# CHRG_2xCell_MCP73213-B6SIMF.net
KiCad netlist of a schematic drawn in Altium Designer
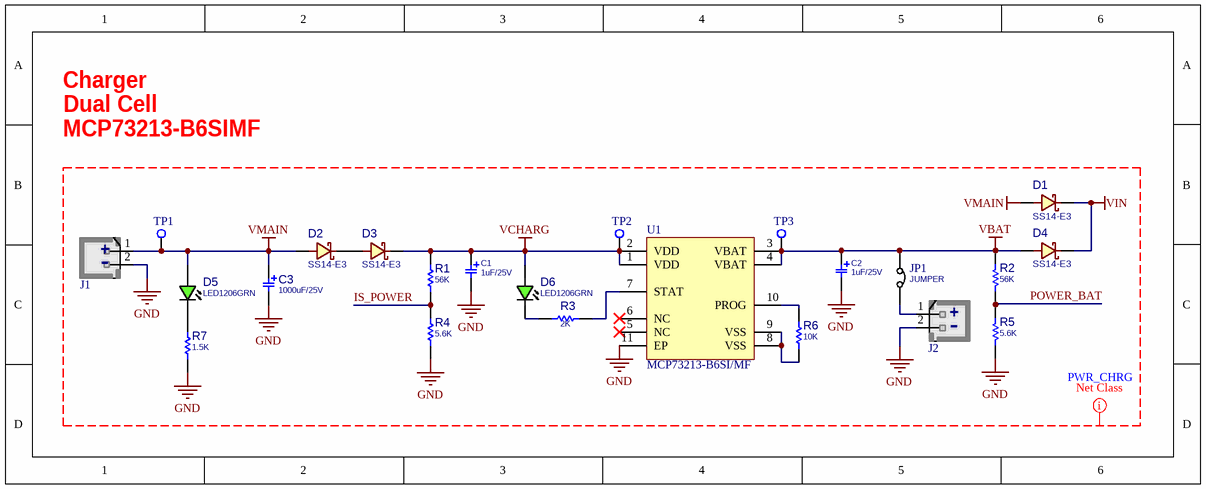
[diagram p0: CHRG 2xCell MCP73213-B6SIMF.SchDoc]

(export (version "E")
  (design (tool "Eeschema 10.0.6"))
  (components
    (comp (ref "C1")
      (value "1uF/25V")
      (footprint "C_TN_A")
      (description "CAP, SMD, TAN")
      (libsource (lib "Passive") (part "CAP_SMD_TAN"))
    )
    (comp (ref "C2")
      (value "1uF/25V")
      (footprint "C_TN_A")
      (description "CAP, SMD, TAN")
      (libsource (lib "Passive") (part "CAP_SMD_TAN"))
    )
    (comp (ref "C3")
      (value "1000uF/25V")
      (footprint "C_EL_10X20")
      (description "CAP, THD, ELEC")
      (fields (field (name "MANF_P#") "MANF_PART#") (field (name "MANF") "MANF"))
      (libsource (lib "Passive") (part "CAP_THD_EL"))
    )
    (comp (ref "D1")
      (value "SS14-E3")
      (footprint "D_SMA")
      (description "DIODE, SCHOTTKY, 40V, 1A")
      (fields (field (name "MANF") "Vishay"))
      (libsource (lib "Diode") (part "DIODE_SMD_SCHOTTKY_SS14-E3"))
    )
    (comp (ref "D2")
      (value "SS14-E3")
      (footprint "D_SMA")
      (description "DIODE, SCHOTTKY, 40V, 1A")
      (fields (field (name "MANF") "Vishay"))
      (libsource (lib "Diode") (part "DIODE_SMD_SCHOTTKY_SS14-E3"))
    )
    (comp (ref "D3")
      (value "SS14-E3")
      (footprint "D_SMA")
      (description "DIODE, SCHOTTKY, 40V, 1A")
      (fields (field (name "MANF") "Vishay"))
      (libsource (lib "Diode") (part "DIODE_SMD_SCHOTTKY_SS14-E3"))
    )
    (comp (ref "D4")
      (value "SS14-E3")
      (footprint "D_SMA")
      (description "DIODE, SCHOTTKY, 40V, 1A")
      (fields (field (name "MANF") "Vishay"))
      (libsource (lib "Diode") (part "DIODE_SMD_SCHOTTKY_SS14-E3"))
    )
    (comp (ref "D5")
      (value "LED1206GRN")
      (footprint "LED1206GRN")
      (description "LED, SMD, 1206, GREEN")
      (libsource (lib "LED") (part "LED_SMD_1206_GRN"))
    )
    (comp (ref "D6")
      (value "LED1206GRN")
      (footprint "LED1206GRN")
      (description "LED, SMD, 1206, GREEN")
      (libsource (lib "LED") (part "LED_SMD_1206_GRN"))
    )
    (comp (ref "J1")
      (value "HHDR_2")
      (footprint "XH_2")
      (description "CONN, CNT, pitch: 2.54mm, 2POS")
      (libsource (lib "PW Components") (part "CONN_PW_POWER_CNT_254_1X2"))
    )
    (comp (ref "J2")
      (value "HHDR_2")
      (footprint "XH_2")
      (description "CONN, CNT, pitch: 2.54mm, 2POS")
      (libsource (lib "") (part "CONN_PW_POWER_CNT_254_1X2_1"))
    )
    (comp (ref "JP1")
      (value "JUMPER")
      (footprint "JP_2_BLK")
      (description "JUMPER, HEADER 2PIN")
      (fields (field (name "MANF") "MANF") (field (name "MANF_P#") "MANF_P#"))
      (libsource (lib "PW Components") (part "JUMPER_HDR_2P"))
    )
    (comp (ref "R1")
      (value "56K")
      (footprint "R0603S")
      (description "RES, SMD")
      (fields (field (name "MANF_P#") "RK73H1ETTP4701F") (field (name "MANF") "KOA SPEER"))
      (libsource (lib "Passive") (part "RES_SMD"))
    )
    (comp (ref "R2")
      (value "56K")
      (footprint "R0603S")
      (description "RES, SMD")
      (fields (field (name "MANF_P#") "RK73H1ETTP4701F") (field (name "MANF") "KOA SPEER"))
      (libsource (lib "Passive") (part "RES_SMD"))
    )
    (comp (ref "R3")
      (value "2K")
      (footprint "R0603S")
      (description "RES, SMD")
      (fields (field (name "MANF_P#") "RK73H1ETTP4701F") (field (name "MANF") "KOA SPEER"))
      (libsource (lib "Passive") (part "RES_SMD"))
    )
    (comp (ref "R4")
      (value "5.6K")
      (footprint "R0603S")
      (description "RES, SMD")
      (fields (field (name "MANF_P#") "RK73H1ETTP4701F") (field (name "MANF") "KOA SPEER"))
      (libsource (lib "Passive") (part "RES_SMD"))
    )
    (comp (ref "R5")
      (value "5.6K")
      (footprint "R0603S")
      (description "RES, SMD")
      (fields (field (name "MANF_P#") "RK73H1ETTP4701F") (field (name "MANF") "KOA SPEER"))
      (libsource (lib "Passive") (part "RES_SMD"))
    )
    (comp (ref "R6")
      (value "10K")
      (footprint "R0603S")
      (description "RES, SMD")
      (fields (field (name "MANF_P#") "RK73H1ETTP4701F") (field (name "MANF") "KOA SPEER"))
      (libsource (lib "Passive") (part "RES_SMD"))
    )
    (comp (ref "R7")
      (value "1.5K")
      (footprint "R0603S")
      (description "RES, SMD")
      (fields (field (name "MANF_P#") "RK73H1ETTP4701F") (field (name "MANF") "KOA SPEER"))
      (libsource (lib "Passive") (part "RES_SMD"))
    )
    (comp (ref "TP1")
      (value "Test Point")
      (footprint "TPSMD_C1")
      (libsource (lib "Passives") (part "Test Point"))
    )
    (comp (ref "TP2")
      (value "Test Point")
      (footprint "TPSMD_C1")
      (libsource (lib "Passives") (part "Test Point"))
    )
    (comp (ref "TP3")
      (value "Test Point")
      (footprint "TPSMD_C1")
      (libsource (lib "Passives") (part "Test Point"))
    )
    (comp (ref "U1")
      (value "MCP73213-B6SI/MF")
      (footprint "SON50_10T_3X3")
      (fields (field (name "PUBLISHER") "Altium Limited"))
      (libsource (lib "Microchip Power Mgt Battery Management") (part "MCP73213-B6SI/MF"))
    )
  )
  (nets
    (net (code "1") (name "/IS_POWER") (class "Default")
      (node (ref "R1") (pin "1") (pinfunction "1_1") (pintype "passive"))
      (node (ref "R4") (pin "2") (pinfunction "2_2") (pintype "passive"))
    )
    (net (code "2") (name "/POWER_BAT") (class "Default")
      (node (ref "R2") (pin "1") (pinfunction "1_1") (pintype "passive"))
      (node (ref "R5") (pin "2") (pinfunction "2_2") (pintype "passive"))
    )
    (net (code "3") (name "GND") (class "Default")
      (node (ref "C1") (pin "2") (pinfunction "2_2") (pintype "passive"))
      (node (ref "C2") (pin "2") (pinfunction "2_2") (pintype "passive"))
      (node (ref "C3") (pin "2") (pinfunction "2_2") (pintype "passive"))
      (node (ref "J1") (pin "2") (pinfunction "2_2") (pintype "passive"))
      (node (ref "J2") (pin "2") (pinfunction "2_2") (pintype "passive"))
      (node (ref "R4") (pin "1") (pinfunction "1_1") (pintype "passive"))
      (node (ref "R5") (pin "1") (pinfunction "1_1") (pintype "passive"))
      (node (ref "R7") (pin "1") (pinfunction "1_1") (pintype "passive"))
      (node (ref "U1") (pin "11") (pinfunction "EP_11") (pintype "passive"))
    )
    (net (code "4") (name "Net-(D2-Pad2)") (class "Default")
      (node (ref "D2") (pin "2") (pinfunction "2_2") (pintype "passive"))
      (node (ref "D3") (pin "1") (pinfunction "1_1") (pintype "passive"))
    )
    (net (code "5") (name "Net-(D5-CATHODE)") (class "Default")
      (node (ref "D5") (pin "2") (pinfunction "CATHODE_2") (pintype "passive"))
      (node (ref "R7") (pin "2") (pinfunction "2_2") (pintype "passive"))
    )
    (net (code "6") (name "Net-(D6-CATHODE)") (class "Default")
      (node (ref "D6") (pin "2") (pinfunction "CATHODE_2") (pintype "passive"))
      (node (ref "R3") (pin "2") (pinfunction "2_2") (pintype "passive"))
    )
    (net (code "7") (name "Net-(J2-Pad1)") (class "Default")
      (node (ref "J2") (pin "1") (pinfunction "1_1") (pintype "passive"))
      (node (ref "JP1") (pin "2") (pinfunction "2_2") (pintype "passive"))
    )
    (net (code "8") (name "Net-(R6-Pad2)") (class "Default")
      (node (ref "R6") (pin "2") (pinfunction "2_2") (pintype "passive"))
      (node (ref "U1") (pin "8") (pinfunction "VSS_8") (pintype "passive"))
      (node (ref "U1") (pin "9") (pinfunction "VSS_9") (pintype "passive"))
    )
    (net (code "9") (name "Net-(U1-PROG)") (class "Default")
      (node (ref "R6") (pin "1") (pinfunction "1_1") (pintype "passive"))
      (node (ref "U1") (pin "10") (pinfunction "PROG_10") (pintype "passive"))
    )
    (net (code "10") (name "Net-(U1-STAT)") (class "Default")
      (node (ref "R3") (pin "1") (pinfunction "1_1") (pintype "passive"))
      (node (ref "U1") (pin "7") (pinfunction "STAT_7") (pintype "passive"))
    )
    (net (code "11") (name "VBAT") (class "Default")
      (node (ref "C2") (pin "1") (pinfunction "1_1") (pintype "passive"))
      (node (ref "D4") (pin "1") (pinfunction "1_1") (pintype "passive"))
      (node (ref "JP1") (pin "1") (pinfunction "1_1") (pintype "passive"))
      (node (ref "R2") (pin "2") (pinfunction "2_2") (pintype "passive"))
      (node (ref "TP3") (pin "1") (pinfunction "TP_1") (pintype "passive"))
      (node (ref "U1") (pin "3") (pinfunction "VBAT_3") (pintype "passive"))
      (node (ref "U1") (pin "4") (pinfunction "VBAT_4") (pintype "passive"))
    )
    (net (code "12") (name "VCHARG") (class "Default")
      (node (ref "C1") (pin "1") (pinfunction "1_1") (pintype "passive"))
      (node (ref "D3") (pin "2") (pinfunction "2_2") (pintype "passive"))
      (node (ref "D6") (pin "1") (pinfunction "ANODE_1") (pintype "passive"))
      (node (ref "R1") (pin "2") (pinfunction "2_2") (pintype "passive"))
      (node (ref "TP2") (pin "1") (pinfunction "TP_1") (pintype "passive"))
      (node (ref "U1") (pin "1") (pinfunction "VDD_1") (pintype "passive"))
      (node (ref "U1") (pin "2") (pinfunction "VDD_2") (pintype "passive"))
    )
    (net (code "13") (name "VIN") (class "Default")
      (node (ref "D1") (pin "2") (pinfunction "2_2") (pintype "passive"))
      (node (ref "D4") (pin "2") (pinfunction "2_2") (pintype "passive"))
    )
    (net (code "14") (name "VMAIN") (class "Default")
      (node (ref "C3") (pin "1") (pinfunction "1_1") (pintype "passive"))
      (node (ref "D1") (pin "1") (pinfunction "1_1") (pintype "passive"))
      (node (ref "D2") (pin "1") (pinfunction "1_1") (pintype "passive"))
      (node (ref "D5") (pin "1") (pinfunction "ANODE_1") (pintype "passive"))
      (node (ref "J1") (pin "1") (pinfunction "1_1") (pintype "passive"))
      (node (ref "TP1") (pin "1") (pinfunction "TP_1") (pintype "passive"))
    )
    (net (code "15") (name "unconnected-(U1-NC-Pad5)") (class "Default")
      (node (ref "U1") (pin "5") (pinfunction "NC_5") (pintype "passive+no_connect"))
    )
    (net (code "16") (name "unconnected-(U1-NC-Pad6)") (class "Default")
      (node (ref "U1") (pin "6") (pinfunction "NC_6") (pintype "passive+no_connect"))
    )
  )
)
